# GPS_Receiver.net
KiCad netlist of a schematic drawn in Altium Designer
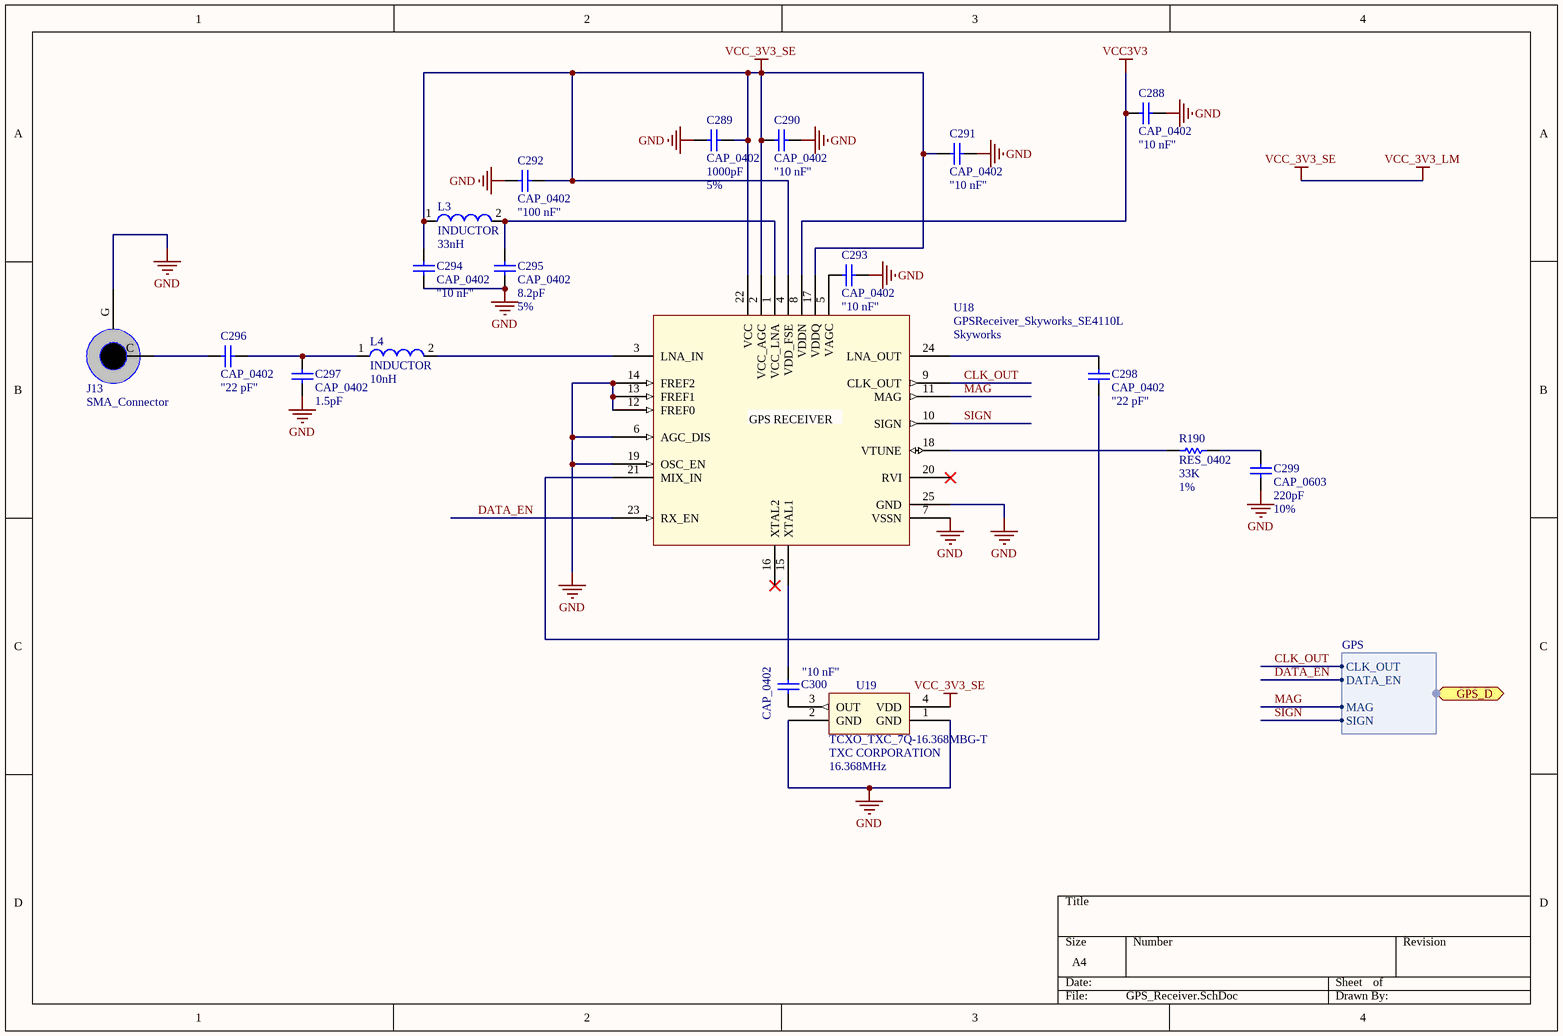
[diagram p0: GPS_Receiver.SchDoc]

(export (version "E")
  (design (tool "Eeschema 10.0.6"))
  (components
    (comp (ref "C288")
      (value "CAP_0402")
      (footprint "CAPC0402(1005)60_N")
      (description "C 10 nF 16 V 0402 X7R")
      (fields
        (field (name "ALTIUM_VALUE") "\"10 nF\"")
        (field (name "PART NUMBER") "\"2238 787 15636\"")
        (field (name "MANUFACTURER") "PHYCOMP")
      )
      (libsource (lib "COMRAD_Database") (part "CAP_0402"))
    )
    (comp (ref "C289")
      (value "CAP_0402")
      (footprint "CAPC0402(1005)60_N")
      (description "CAP CER 1000PF 25V 5% 0402")
      (fields
        (field (name "ALTIUM_VALUE") "1000pF")
        (field (name "TOLERANCE") "5%")
        (field (name "PART NUMBER") "TMK105SD102JV-F")
        (field (name "MANUFACTURER") "Taiyo Yuden")
      )
      (libsource (lib "COMRAD_Database") (part "CAP_0402"))
    )
    (comp (ref "C290")
      (value "CAP_0402")
      (footprint "CAPC0402(1005)60_N")
      (description "C 10 nF 16 V 0402 X7R")
      (fields
        (field (name "ALTIUM_VALUE") "\"10 nF\"")
        (field (name "PART NUMBER") "\"2238 787 15636\"")
        (field (name "MANUFACTURER") "PHYCOMP")
      )
      (libsource (lib "COMRAD_Database") (part "CAP_0402"))
    )
    (comp (ref "C291")
      (value "CAP_0402")
      (footprint "CAPC0402(1005)60_N")
      (description "C 10 nF 16 V 0402 X7R")
      (fields
        (field (name "ALTIUM_VALUE") "\"10 nF\"")
        (field (name "PART NUMBER") "\"2238 787 15636\"")
        (field (name "MANUFACTURER") "PHYCOMP")
      )
      (libsource (lib "COMRAD_Database") (part "CAP_0402"))
    )
    (comp (ref "C292")
      (value "CAP_0402")
      (footprint "CAPC0402(1005)60_N")
      (description "C 100 nF 16 V 0402 X5R")
      (fields
        (field (name "ALTIUM_VALUE") "\"100 nF\"")
        (field (name "PART NUMBER") "\"C0402C104K8PAC\"")
        (field (name "MANUFACTURER") "KEMET")
      )
      (libsource (lib "COMRAD_Database") (part "CAP_0402"))
    )
    (comp (ref "C293")
      (value "CAP_0402")
      (footprint "CAPC0402(1005)60_N")
      (description "C 10 nF 16 V 0402 X7R")
      (fields
        (field (name "ALTIUM_VALUE") "\"10 nF\"")
        (field (name "PART NUMBER") "\"2238 787 15636\"")
        (field (name "MANUFACTURER") "PHYCOMP")
      )
      (libsource (lib "COMRAD_Database") (part "CAP_0402"))
    )
    (comp (ref "C294")
      (value "CAP_0402")
      (footprint "CAPC0402(1005)60_N")
      (description "C 10 nF 16 V 0402 X7R")
      (fields
        (field (name "ALTIUM_VALUE") "\"10 nF\"")
        (field (name "PART NUMBER") "\"2238 787 15636\"")
        (field (name "MANUFACTURER") "PHYCOMP")
      )
      (libsource (lib "COMRAD_Database") (part "CAP_0402"))
    )
    (comp (ref "C295")
      (value "CAP_0402")
      (footprint "CAPC0402(1005)60_N")
      (description "CAP CER 8.2PF 25V 5% NP0 0402")
      (fields
        (field (name "ALTIUM_VALUE") "8.2pF")
        (field (name "TOLERANCE") "5%")
        (field (name "PART NUMBER") "C0402C829J3GACAUTO")
        (field (name "MANUFACTURER") "Kemet")
      )
      (libsource (lib "COMRAD_Database") (part "CAP_0402"))
    )
    (comp (ref "C296")
      (value "CAP_0402")
      (footprint "CAPC0402(1005)60_N")
      (description "C 22 pF 50 V 0402 NP0")
      (fields
        (field (name "ALTIUM_VALUE") "\"22 pF\"")
        (field (name "PART NUMBER") "\"GRM1555C1H220JZ01D\"")
        (field (name "MANUFACTURER") "MURATA")
      )
      (libsource (lib "COMRAD_Database") (part "CAP_0402"))
    )
    (comp (ref "C297")
      (value "CAP_0402")
      (footprint "CAPC0402(1005)60_N")
      (description "CAP CER 1.5PF 50V NP0 0402")
      (fields
        (field (name "ALTIUM_VALUE") "1.5pF")
        (field (name "PART NUMBER") "GJM1555C1H1R5CB01D")
        (field (name "MANUFACTURER") "Murata Electronics North America")
      )
      (libsource (lib "COMRAD_Database") (part "CAP_0402"))
    )
    (comp (ref "C298")
      (value "CAP_0402")
      (footprint "CAPC0402(1005)60_N")
      (description "C 22 pF 50 V 0402 NP0")
      (fields
        (field (name "ALTIUM_VALUE") "\"22 pF\"")
        (field (name "PART NUMBER") "\"GRM1555C1H220JZ01D\"")
        (field (name "MANUFACTURER") "MURATA")
      )
      (libsource (lib "COMRAD_Database") (part "CAP_0402"))
    )
    (comp (ref "C299")
      (value "CAP_0603")
      (footprint "CAPC0603(1608)100_N:CAPC0603(1608)100_N")
      (description "CAP CER 220PF 50V 10% NP0 0603")
      (fields
        (field (name "ALTIUM_VALUE") "220pF")
        (field (name "TOLERANCE") "10%")
        (field (name "PART NUMBER") "VJ0603D221KXAAJ")
        (field (name "MANUFACTURER") "Vishay Vitramon")
      )
      (libsource (lib "COMRAD_Database") (part "CAP_0603"))
    )
    (comp (ref "C300")
      (value "CAP_0402")
      (footprint "CAPC0402(1005)60_N")
      (description "C 10 nF 16 V 0402 X7R")
      (fields
        (field (name "ALTIUM_VALUE") "\"10 nF\"")
        (field (name "PART NUMBER") "\"2238 787 15636\"")
        (field (name "MANUFACTURER") "PHYCOMP")
      )
      (libsource (lib "COMRAD_Database") (part "CAP_0402"))
    )
    (comp (ref "J13")
      (value "SMA_Connector")
      (footprint "Connector_SMA_Amphenol_132255_Edgemount")
      (description "CONN RCPT SMA END LAUNCH PCB")
      (fields (field (name "PART NUMBER") "132255") (field (name "MANUFACTURER") "Amphenol Connex"))
      (libsource (lib "COMRAD_Database") (part "SMA_Connector"))
    )
    (comp (ref "L3")
      (value "INDUCTOR")
      (footprint "Inductor0402(1005)")
      (description "INDUCTOR, 33nH, 0402, DCR 0.06,")
      (fields
        (field (name "ALTIUM_VALUE") "33nH")
        (field (name "PART NUMBER") "0402AF-330")
        (field (name "MANUFACTURER") "Coilcraft")
      )
      (libsource (lib "COMRAD_Database") (part "SYM-0029-00001-1"))
    )
    (comp (ref "L4")
      (value "INDUCTOR")
      (footprint "Inductor0402(1005)")
      (description "INDUCTOR, 10nH, 0402, DCR 0.2,")
      (fields
        (field (name "ALTIUM_VALUE") "10nH")
        (field (name "PART NUMBER") "0402CS-10N")
        (field (name "MANUFACTURER") "Coilcraft")
      )
      (libsource (lib "COMRAD_Database") (part "SYM-0029-00001-1"))
    )
    (comp (ref "R190")
      (value "RES_0402")
      (footprint "RESC0402(1005)_N")
      (description "33K ohms, 1% 1/16W, 0402")
      (fields
        (field (name "ALTIUM_VALUE") "33K")
        (field (name "TOLERANCE") "1%")
        (field (name "PART NUMBER") "RK73H1ETTP3302F")
        (field (name "MANUFACTURER") "KOA Speer Electronics")
      )
      (libsource (lib "COMRAD_Database") (part "RES_0402"))
    )
    (comp (ref "U18")
      (value "GPSReceiver_Skyworks_SE4110L")
      (footprint "GPSReceiver_Skyworks_SE4110L_24QFN")
      (description "High sensitivity / low power GPS and A-GPS,10 mA operating current with 2.7-3.3 V supply")
      (fields (field (name "PART NUMBER") "SE4110L") (field (name "MANUFACTURER") "Skyworks"))
      (libsource (lib "COMRAD_Database") (part "GPSReceiver_Skyworks_SE4110L"))
    )
    (comp (ref "U19")
      (value "TCXO_TXC_7Q-16.368MBG-T")
      (footprint "TCXO_TXC_7Q-16.368MBG-T_4-PIN")
      (description "OSC TCXO 16.368 MHZ 3.3V SMD")
      (fields
        (field (name "PART NUMBER") "7Q-16.368MBG-T")
        (field (name "MANUFACTURER") "TXC CORPORATION")
        (field (name "ALTIUM_VALUE") "16.368MHz")
      )
      (libsource (lib "COMRAD_Database") (part "TCXO_TXC_7Q-16.368MBG-T"))
    )
  )
  (nets
    (net (code "2") (name "/CLK_OUT") (class "Default")
      (node (ref "U18") (pin "9") (pinfunction "CLK_OUT_9") (pintype "output"))
    )
    (net (code "3") (name "/DATA_EN") (class "Default")
      (node (ref "U18") (pin "23") (pinfunction "RX_EN_23") (pintype "input"))
    )
    (net (code "4") (name "/MAG") (class "Default")
      (node (ref "U18") (pin "11") (pinfunction "MAG_11") (pintype "output"))
    )
    (net (code "5") (name "/SIGN") (class "Default")
      (node (ref "U18") (pin "10") (pinfunction "SIGN_10") (pintype "output"))
    )
    (net (code "7") (name "GND") (class "Default")
      (node (ref "C288") (pin "2") (pinfunction "2_2") (pintype "passive"))
      (node (ref "C289") (pin "1") (pinfunction "1_1") (pintype "passive"))
      (node (ref "C290") (pin "1") (pinfunction "1_1") (pintype "passive"))
      (node (ref "C291") (pin "1") (pinfunction "1_1") (pintype "passive"))
      (node (ref "C292") (pin "2") (pinfunction "2_2") (pintype "passive"))
      (node (ref "C293") (pin "1") (pinfunction "1_1") (pintype "passive"))
      (node (ref "C294") (pin "2") (pinfunction "2_2") (pintype "passive"))
      (node (ref "C295") (pin "1") (pinfunction "1_1") (pintype "passive"))
      (node (ref "C297") (pin "1") (pinfunction "1_1") (pintype "passive"))
      (node (ref "C299") (pin "1") (pinfunction "1_1") (pintype "passive"))
      (node (ref "J13") (pin "G") (pinfunction "2_G") (pintype "passive"))
      (node (ref "U18") (pin "12") (pinfunction "FREF0_12") (pintype "input"))
      (node (ref "U18") (pin "13") (pinfunction "FREF1_13") (pintype "input"))
      (node (ref "U18") (pin "14") (pinfunction "FREF2_14") (pintype "input"))
      (node (ref "U18") (pin "19") (pinfunction "OSC_EN_19") (pintype "input"))
      (node (ref "U18") (pin "25") (pinfunction "GND_25") (pintype "power_in"))
      (node (ref "U18") (pin "6") (pinfunction "AGC_DIS_6") (pintype "input"))
      (node (ref "U18") (pin "7") (pinfunction "VSSN_7") (pintype "power_in"))
      (node (ref "U19") (pin "1") (pinfunction "GND_1") (pintype "power_in"))
      (node (ref "U19") (pin "2") (pinfunction "GND_2") (pintype "power_in"))
    )
    (net (code "8") (name "Net-(C296-Pad2)") (class "Default")
      (node (ref "C296") (pin "2") (pinfunction "2_2") (pintype "passive"))
      (node (ref "C297") (pin "2") (pinfunction "2_2") (pintype "passive"))
      (node (ref "L4") (pin "1") (pinfunction "1_1") (pintype "passive"))
    )
    (net (code "9") (name "Net-(C299-Pad2)") (class "Default")
      (node (ref "C299") (pin "2") (pinfunction "2_2") (pintype "passive"))
      (node (ref "R190") (pin "2") (pinfunction "2_2") (pintype "passive"))
    )
    (net (code "10") (name "Net-(J13-1)") (class "Default")
      (node (ref "C296") (pin "1") (pinfunction "1_1") (pintype "passive"))
      (node (ref "J13") (pin "C") (pinfunction "1_C") (pintype "passive"))
    )
    (net (code "11") (name "Net-(U18-LNA_IN)") (class "Default")
      (node (ref "L4") (pin "2") (pinfunction "2_2") (pintype "passive"))
      (node (ref "U18") (pin "3") (pinfunction "LNA_IN_3") (pintype "passive"))
    )
    (net (code "12") (name "Net-(U18-LNA_OUT)") (class "Default")
      (node (ref "C298") (pin "2") (pinfunction "2_2") (pintype "passive"))
      (node (ref "U18") (pin "24") (pinfunction "LNA_OUT_24") (pintype "passive"))
    )
    (net (code "13") (name "Net-(U18-MIX_IN)") (class "Default")
      (node (ref "C298") (pin "1") (pinfunction "1_1") (pintype "passive"))
      (node (ref "U18") (pin "21") (pinfunction "MIX_IN_21") (pintype "passive"))
    )
    (net (code "14") (name "Net-(U18-VAGC)") (class "Default")
      (node (ref "C293") (pin "2") (pinfunction "2_2") (pintype "passive"))
      (node (ref "U18") (pin "5") (pinfunction "VAGC_5") (pintype "passive"))
    )
    (net (code "15") (name "Net-(U18-VCC_LNA)") (class "Default")
      (node (ref "C295") (pin "2") (pinfunction "2_2") (pintype "passive"))
      (node (ref "L3") (pin "2") (pinfunction "2_2") (pintype "passive"))
      (node (ref "U18") (pin "1") (pinfunction "VCC_LNA_1") (pintype "power_in"))
    )
    (net (code "16") (name "Net-(U18-VTUNE)") (class "Default")
      (node (ref "R190") (pin "1") (pinfunction "1_1") (pintype "passive"))
      (node (ref "U18") (pin "18") (pinfunction "VTUNE_18") (pintype "bidirectional"))
    )
    (net (code "17") (name "Net-(U18-XTAL1)") (class "Default")
      (node (ref "C300") (pin "2") (pinfunction "2_2") (pintype "passive"))
      (node (ref "U18") (pin "15") (pinfunction "XTAL1_15") (pintype "passive"))
    )
    (net (code "18") (name "Net-(U19-OUT)") (class "Default")
      (node (ref "C300") (pin "1") (pinfunction "1_1") (pintype "passive"))
      (node (ref "U19") (pin "3") (pinfunction "OUT_3") (pintype "output"))
    )
    (net (code "19") (name "VCC3V3") (class "Default")
      (node (ref "C288") (pin "1") (pinfunction "1_1") (pintype "passive"))
      (node (ref "U18") (pin "8") (pinfunction "VDDN_8") (pintype "power_in"))
    )
    (net (code "20") (name "VCC_3V3_LM") (class "Default")
      (node (ref "C289") (pin "2") (pinfunction "2_2") (pintype "passive"))
      (node (ref "C290") (pin "2") (pinfunction "2_2") (pintype "passive"))
      (node (ref "C291") (pin "2") (pinfunction "2_2") (pintype "passive"))
      (node (ref "C292") (pin "1") (pinfunction "1_1") (pintype "passive"))
      (node (ref "C294") (pin "1") (pinfunction "1_1") (pintype "passive"))
      (node (ref "L3") (pin "1") (pinfunction "1_1") (pintype "passive"))
      (node (ref "U18") (pin "17") (pinfunction "VDDQ_17") (pintype "power_in"))
      (node (ref "U18") (pin "2") (pinfunction "VCC_AGC_2") (pintype "power_in"))
      (node (ref "U18") (pin "22") (pinfunction "VCC_22") (pintype "power_in"))
      (node (ref "U18") (pin "4") (pinfunction "VDD_FSE_4") (pintype "passive"))
      (node (ref "U19") (pin "4") (pinfunction "VDD_4") (pintype "power_in"))
    )
    (net (code "21") (name "unconnected-(U18-RVI-Pad20)") (class "Default")
      (node (ref "U18") (pin "20") (pinfunction "RVI_20") (pintype "passive+no_connect"))
    )
    (net (code "22") (name "unconnected-(U18-XTAL2-Pad16)") (class "Default")
      (node (ref "U18") (pin "16") (pinfunction "XTAL2_16") (pintype "passive+no_connect"))
    )
  )
)
